# 15_HEATER.net
KiCad netlist of a schematic drawn in Altium Designer
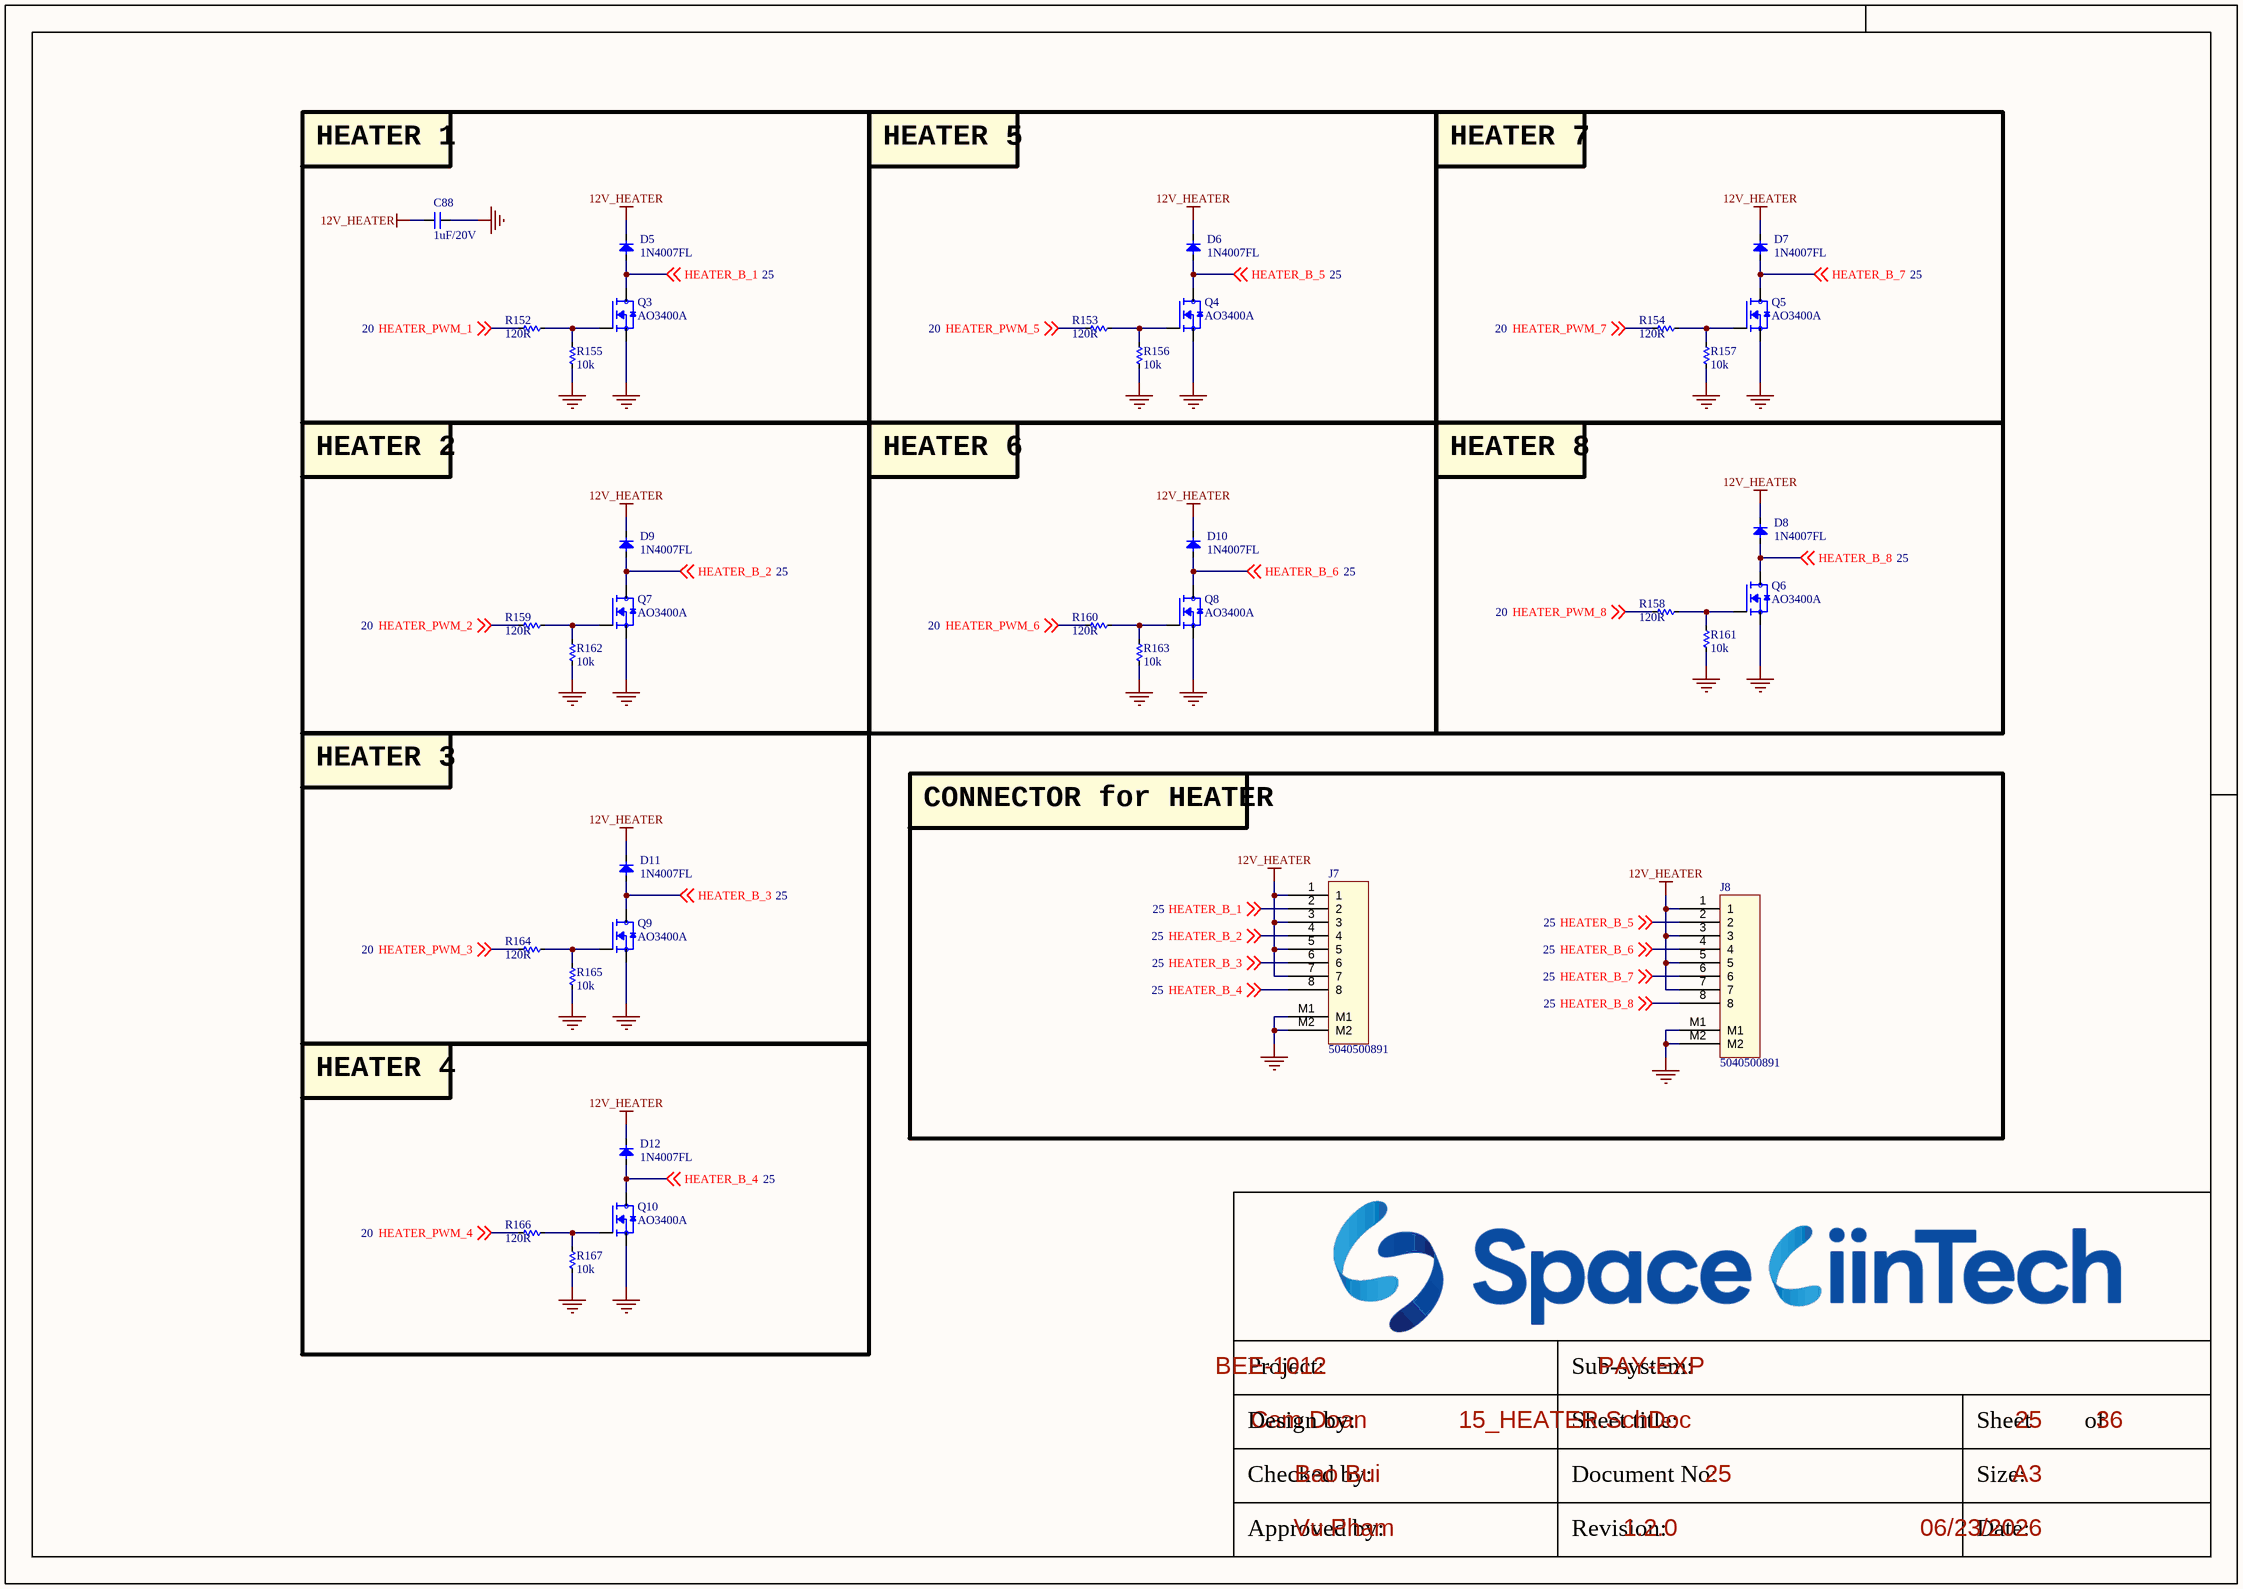
[diagram p0: 15_HEATER.SchDoc]

(export (version "E")
  (design (tool "Eeschema 10.0.6"))
  (components
    (comp (ref "C88")
      (value "1uF/20V")
      (footprint "CAP_C_1005X60")
      (description "CAP")
      (libsource (lib "LABLIB") (part "_CAP_C_2"))
    )
    (comp (ref "D5")
      (value "1N4007FL")
      (footprint "SOD3717X145N")
      (description "Default Diode")
      (fields (field (name "PUBLISHER") "Altium Limited"))
      (libsource (lib "LABLIB") (part "Diode SMD"))
    )
    (comp (ref "D6")
      (value "1N4007FL")
      (footprint "SOD3717X145N")
      (description "Default Diode")
      (fields (field (name "PUBLISHER") "Altium Limited"))
      (libsource (lib "LABLIB") (part "Diode SMD"))
    )
    (comp (ref "D7")
      (value "1N4007FL")
      (footprint "SOD3717X145N")
      (description "Default Diode")
      (fields (field (name "PUBLISHER") "Altium Limited"))
      (libsource (lib "LABLIB") (part "Diode SMD"))
    )
    (comp (ref "D8")
      (value "1N4007FL")
      (footprint "SOD3717X145N")
      (description "Default Diode")
      (fields (field (name "PUBLISHER") "Altium Limited"))
      (libsource (lib "LABLIB") (part "Diode SMD"))
    )
    (comp (ref "D9")
      (value "1N4007FL")
      (footprint "SOD3717X145N")
      (description "Default Diode")
      (fields (field (name "PUBLISHER") "Altium Limited"))
      (libsource (lib "LABLIB") (part "Diode SMD"))
    )
    (comp (ref "D10")
      (value "1N4007FL")
      (footprint "SOD3717X145N")
      (description "Default Diode")
      (fields (field (name "PUBLISHER") "Altium Limited"))
      (libsource (lib "LABLIB") (part "Diode SMD"))
    )
    (comp (ref "D11")
      (value "1N4007FL")
      (footprint "SOD3717X145N")
      (description "Default Diode")
      (fields (field (name "PUBLISHER") "Altium Limited"))
      (libsource (lib "LABLIB") (part "Diode SMD"))
    )
    (comp (ref "D12")
      (value "1N4007FL")
      (footprint "SOD3717X145N")
      (description "Default Diode")
      (fields (field (name "PUBLISHER") "Altium Limited"))
      (libsource (lib "LABLIB") (part "Diode SMD"))
    )
    (comp (ref "J7")
      (value "5040500891")
      (footprint "MOLEX_5040500891")
      (libsource (lib "LABLIB") (part "Header 8x1_2M"))
    )
    (comp (ref "J8")
      (value "5040500891")
      (footprint "MOLEX_5040500891")
      (libsource (lib "LABLIB") (part "Header 8x1_2M"))
    )
    (comp (ref "Q3")
      (value "AO3400A")
      (footprint "SOT95P240X120-3N")
      (description "N-Channel 30 V 5.7A (Ta) 1.4W (Ta) Surface Mount SOT-23-3")
      (fields (field (name "MF") "Alpha & Omega Semiconductor"))
      (libsource (lib "LABLIB") (part "MOSFET_N"))
    )
    (comp (ref "Q4")
      (value "AO3400A")
      (footprint "SOT95P240X120-3N")
      (description "N-Channel 30 V 5.7A (Ta) 1.4W (Ta) Surface Mount SOT-23-3")
      (fields (field (name "MF") "Alpha & Omega Semiconductor"))
      (libsource (lib "LABLIB") (part "MOSFET_N"))
    )
    (comp (ref "Q5")
      (value "AO3400A")
      (footprint "SOT95P240X120-3N")
      (description "N-Channel 30 V 5.7A (Ta) 1.4W (Ta) Surface Mount SOT-23-3")
      (fields (field (name "MF") "Alpha & Omega Semiconductor"))
      (libsource (lib "LABLIB") (part "MOSFET_N"))
    )
    (comp (ref "Q6")
      (value "AO3400A")
      (footprint "SOT95P240X120-3N")
      (description "N-Channel 30 V 5.7A (Ta) 1.4W (Ta) Surface Mount SOT-23-3")
      (fields (field (name "MF") "Alpha & Omega Semiconductor"))
      (libsource (lib "LABLIB") (part "MOSFET_N"))
    )
    (comp (ref "Q7")
      (value "AO3400A")
      (footprint "SOT95P240X120-3N")
      (description "N-Channel 30 V 5.7A (Ta) 1.4W (Ta) Surface Mount SOT-23-3")
      (fields (field (name "MF") "Alpha & Omega Semiconductor"))
      (libsource (lib "LABLIB") (part "MOSFET_N"))
    )
    (comp (ref "Q8")
      (value "AO3400A")
      (footprint "SOT95P240X120-3N")
      (description "N-Channel 30 V 5.7A (Ta) 1.4W (Ta) Surface Mount SOT-23-3")
      (fields (field (name "MF") "Alpha & Omega Semiconductor"))
      (libsource (lib "LABLIB") (part "MOSFET_N"))
    )
    (comp (ref "Q9")
      (value "AO3400A")
      (footprint "SOT95P240X120-3N")
      (description "N-Channel 30 V 5.7A (Ta) 1.4W (Ta) Surface Mount SOT-23-3")
      (fields (field (name "MF") "Alpha & Omega Semiconductor"))
      (libsource (lib "LABLIB") (part "MOSFET_N"))
    )
    (comp (ref "Q10")
      (value "AO3400A")
      (footprint "SOT95P240X120-3N")
      (description "N-Channel 30 V 5.7A (Ta) 1.4W (Ta) Surface Mount SOT-23-3")
      (fields (field (name "MF") "Alpha & Omega Semiconductor"))
      (libsource (lib "LABLIB") (part "MOSFET_N"))
    )
    (comp (ref "R152")
      (value "120R")
      (footprint "RES_C_1005X40")
      (description "RES")
      (libsource (lib "LABLIB") (part "_RES_B_2"))
    )
    (comp (ref "R153")
      (value "120R")
      (footprint "RES_C_1005X40")
      (description "RES")
      (libsource (lib "LABLIB") (part "_RES_B_2"))
    )
    (comp (ref "R154")
      (value "120R")
      (footprint "RES_C_1005X40")
      (description "RES")
      (libsource (lib "LABLIB") (part "_RES_B_2"))
    )
    (comp (ref "R155")
      (value "10k")
      (footprint "RES_C_1005X40")
      (description "RES")
      (libsource (lib "LABLIB") (part "_RES_B_2"))
    )
    (comp (ref "R156")
      (value "10k")
      (footprint "RES_C_1005X40")
      (description "RES")
      (libsource (lib "LABLIB") (part "_RES_B_2"))
    )
    (comp (ref "R157")
      (value "10k")
      (footprint "RES_C_1005X40")
      (description "RES")
      (libsource (lib "LABLIB") (part "_RES_B_2"))
    )
    (comp (ref "R158")
      (value "120R")
      (footprint "RES_C_1005X40")
      (description "RES")
      (libsource (lib "LABLIB") (part "_RES_B_2"))
    )
    (comp (ref "R159")
      (value "120R")
      (footprint "RES_C_1005X40")
      (description "RES")
      (libsource (lib "LABLIB") (part "_RES_B_2"))
    )
    (comp (ref "R160")
      (value "120R")
      (footprint "RES_C_1005X40")
      (description "RES")
      (libsource (lib "LABLIB") (part "_RES_B_2"))
    )
    (comp (ref "R161")
      (value "10k")
      (footprint "RES_C_1005X40")
      (description "RES")
      (libsource (lib "LABLIB") (part "_RES_B_2"))
    )
    (comp (ref "R162")
      (value "10k")
      (footprint "RES_C_1005X40")
      (description "RES")
      (libsource (lib "LABLIB") (part "_RES_B_2"))
    )
    (comp (ref "R163")
      (value "10k")
      (footprint "RES_C_1005X40")
      (description "RES")
      (libsource (lib "LABLIB") (part "_RES_B_2"))
    )
    (comp (ref "R164")
      (value "120R")
      (footprint "RES_C_1005X40")
      (description "RES")
      (libsource (lib "LABLIB") (part "_RES_B_2"))
    )
    (comp (ref "R165")
      (value "10k")
      (footprint "RES_C_1005X40")
      (description "RES")
      (libsource (lib "LABLIB") (part "_RES_B_2"))
    )
    (comp (ref "R166")
      (value "120R")
      (footprint "RES_C_1005X40")
      (description "RES")
      (libsource (lib "LABLIB") (part "_RES_B_2"))
    )
    (comp (ref "R167")
      (value "10k")
      (footprint "RES_C_1005X40")
      (description "RES")
      (libsource (lib "LABLIB") (part "_RES_B_2"))
    )
  )
  (nets
    (net (code "1") (name "12V_HEATER") (class "Default")
      (node (ref "C88") (pin "2") (pinfunction "2_2") (pintype "passive"))
      (node (ref "D10") (pin "1") (pinfunction "K_1") (pintype "passive"))
      (node (ref "D11") (pin "1") (pinfunction "K_1") (pintype "passive"))
      (node (ref "D12") (pin "1") (pinfunction "K_1") (pintype "passive"))
      (node (ref "D5") (pin "1") (pinfunction "K_1") (pintype "passive"))
      (node (ref "D6") (pin "1") (pinfunction "K_1") (pintype "passive"))
      (node (ref "D7") (pin "1") (pinfunction "K_1") (pintype "passive"))
      (node (ref "D8") (pin "1") (pinfunction "K_1") (pintype "passive"))
      (node (ref "D9") (pin "1") (pinfunction "K_1") (pintype "passive"))
      (node (ref "J7") (pin "1") (pinfunction "1_1") (pintype "passive"))
      (node (ref "J7") (pin "3") (pinfunction "3_3") (pintype "passive"))
      (node (ref "J7") (pin "5") (pinfunction "5_5") (pintype "passive"))
      (node (ref "J7") (pin "7") (pinfunction "7_7") (pintype "passive"))
      (node (ref "J8") (pin "1") (pinfunction "1_1") (pintype "passive"))
      (node (ref "J8") (pin "3") (pinfunction "3_3") (pintype "passive"))
      (node (ref "J8") (pin "5") (pinfunction "5_5") (pintype "passive"))
      (node (ref "J8") (pin "7") (pinfunction "7_7") (pintype "passive"))
    )
    (net (code "2") (name "GND") (class "Default")
      (node (ref "C88") (pin "1") (pinfunction "1_1") (pintype "passive"))
      (node (ref "J7") (pin "M1") (pinfunction "M1_M1") (pintype "passive"))
      (node (ref "J7") (pin "M2") (pinfunction "M2_M2") (pintype "passive"))
      (node (ref "J8") (pin "M1") (pinfunction "M1_M1") (pintype "passive"))
      (node (ref "J8") (pin "M2") (pinfunction "M2_M2") (pintype "passive"))
      (node (ref "Q10") (pin "2") (pinfunction "S_2") (pintype "passive"))
      (node (ref "Q3") (pin "2") (pinfunction "S_2") (pintype "passive"))
      (node (ref "Q4") (pin "2") (pinfunction "S_2") (pintype "passive"))
      (node (ref "Q5") (pin "2") (pinfunction "S_2") (pintype "passive"))
      (node (ref "Q6") (pin "2") (pinfunction "S_2") (pintype "passive"))
      (node (ref "Q7") (pin "2") (pinfunction "S_2") (pintype "passive"))
      (node (ref "Q8") (pin "2") (pinfunction "S_2") (pintype "passive"))
      (node (ref "Q9") (pin "2") (pinfunction "S_2") (pintype "passive"))
      (node (ref "R155") (pin "1") (pinfunction "1_1") (pintype "passive"))
      (node (ref "R156") (pin "1") (pinfunction "1_1") (pintype "passive"))
      (node (ref "R157") (pin "1") (pinfunction "1_1") (pintype "passive"))
      (node (ref "R161") (pin "1") (pinfunction "1_1") (pintype "passive"))
      (node (ref "R162") (pin "1") (pinfunction "1_1") (pintype "passive"))
      (node (ref "R163") (pin "1") (pinfunction "1_1") (pintype "passive"))
      (node (ref "R165") (pin "1") (pinfunction "1_1") (pintype "passive"))
      (node (ref "R167") (pin "1") (pinfunction "1_1") (pintype "passive"))
    )
    (net (code "3") (name "HEATER_B_1") (class "Default")
      (node (ref "D5") (pin "2") (pinfunction "A_2") (pintype "passive"))
      (node (ref "J7") (pin "2") (pinfunction "2_2") (pintype "passive"))
      (node (ref "Q3") (pin "3") (pinfunction "D_3") (pintype "passive"))
    )
    (net (code "4") (name "HEATER_B_2") (class "Default")
      (node (ref "D9") (pin "2") (pinfunction "A_2") (pintype "passive"))
      (node (ref "J7") (pin "4") (pinfunction "4_4") (pintype "passive"))
      (node (ref "Q7") (pin "3") (pinfunction "D_3") (pintype "passive"))
    )
    (net (code "5") (name "HEATER_B_3") (class "Default")
      (node (ref "D11") (pin "2") (pinfunction "A_2") (pintype "passive"))
      (node (ref "J7") (pin "6") (pinfunction "6_6") (pintype "passive"))
      (node (ref "Q9") (pin "3") (pinfunction "D_3") (pintype "passive"))
    )
    (net (code "6") (name "HEATER_B_4") (class "Default")
      (node (ref "D12") (pin "2") (pinfunction "A_2") (pintype "passive"))
      (node (ref "J7") (pin "8") (pinfunction "8_8") (pintype "passive"))
      (node (ref "Q10") (pin "3") (pinfunction "D_3") (pintype "passive"))
    )
    (net (code "7") (name "HEATER_B_5") (class "Default")
      (node (ref "D6") (pin "2") (pinfunction "A_2") (pintype "passive"))
      (node (ref "J8") (pin "2") (pinfunction "2_2") (pintype "passive"))
      (node (ref "Q4") (pin "3") (pinfunction "D_3") (pintype "passive"))
    )
    (net (code "8") (name "HEATER_B_6") (class "Default")
      (node (ref "D10") (pin "2") (pinfunction "A_2") (pintype "passive"))
      (node (ref "J8") (pin "4") (pinfunction "4_4") (pintype "passive"))
      (node (ref "Q8") (pin "3") (pinfunction "D_3") (pintype "passive"))
    )
    (net (code "9") (name "HEATER_B_7") (class "Default")
      (node (ref "D7") (pin "2") (pinfunction "A_2") (pintype "passive"))
      (node (ref "J8") (pin "6") (pinfunction "6_6") (pintype "passive"))
      (node (ref "Q5") (pin "3") (pinfunction "D_3") (pintype "passive"))
    )
    (net (code "10") (name "HEATER_B_8") (class "Default")
      (node (ref "D8") (pin "2") (pinfunction "A_2") (pintype "passive"))
      (node (ref "J8") (pin "8") (pinfunction "8_8") (pintype "passive"))
      (node (ref "Q6") (pin "3") (pinfunction "D_3") (pintype "passive"))
    )
    (net (code "11") (name "HEATER_PWM_1") (class "Default")
      (node (ref "R152") (pin "1") (pinfunction "1_1") (pintype "passive"))
    )
    (net (code "12") (name "HEATER_PWM_2") (class "Default")
      (node (ref "R159") (pin "1") (pinfunction "1_1") (pintype "passive"))
    )
    (net (code "13") (name "HEATER_PWM_3") (class "Default")
      (node (ref "R164") (pin "1") (pinfunction "1_1") (pintype "passive"))
    )
    (net (code "14") (name "HEATER_PWM_4") (class "Default")
      (node (ref "R166") (pin "1") (pinfunction "1_1") (pintype "passive"))
    )
    (net (code "15") (name "HEATER_PWM_5") (class "Default")
      (node (ref "R153") (pin "1") (pinfunction "1_1") (pintype "passive"))
    )
    (net (code "16") (name "HEATER_PWM_6") (class "Default")
      (node (ref "R160") (pin "1") (pinfunction "1_1") (pintype "passive"))
    )
    (net (code "17") (name "HEATER_PWM_7") (class "Default")
      (node (ref "R154") (pin "1") (pinfunction "1_1") (pintype "passive"))
    )
    (net (code "18") (name "HEATER_PWM_8") (class "Default")
      (node (ref "R158") (pin "1") (pinfunction "1_1") (pintype "passive"))
    )
    (net (code "19") (name "Net-(Q3-G)") (class "Default")
      (node (ref "Q3") (pin "1") (pinfunction "G_1") (pintype "passive"))
      (node (ref "R152") (pin "2") (pinfunction "2_2") (pintype "passive"))
      (node (ref "R155") (pin "2") (pinfunction "2_2") (pintype "passive"))
    )
    (net (code "20") (name "Net-(Q4-G)") (class "Default")
      (node (ref "Q4") (pin "1") (pinfunction "G_1") (pintype "passive"))
      (node (ref "R153") (pin "2") (pinfunction "2_2") (pintype "passive"))
      (node (ref "R156") (pin "2") (pinfunction "2_2") (pintype "passive"))
    )
    (net (code "21") (name "Net-(Q5-G)") (class "Default")
      (node (ref "Q5") (pin "1") (pinfunction "G_1") (pintype "passive"))
      (node (ref "R154") (pin "2") (pinfunction "2_2") (pintype "passive"))
      (node (ref "R157") (pin "2") (pinfunction "2_2") (pintype "passive"))
    )
    (net (code "22") (name "Net-(Q6-G)") (class "Default")
      (node (ref "Q6") (pin "1") (pinfunction "G_1") (pintype "passive"))
      (node (ref "R158") (pin "2") (pinfunction "2_2") (pintype "passive"))
      (node (ref "R161") (pin "2") (pinfunction "2_2") (pintype "passive"))
    )
    (net (code "23") (name "Net-(Q7-G)") (class "Default")
      (node (ref "Q7") (pin "1") (pinfunction "G_1") (pintype "passive"))
      (node (ref "R159") (pin "2") (pinfunction "2_2") (pintype "passive"))
      (node (ref "R162") (pin "2") (pinfunction "2_2") (pintype "passive"))
    )
    (net (code "24") (name "Net-(Q8-G)") (class "Default")
      (node (ref "Q8") (pin "1") (pinfunction "G_1") (pintype "passive"))
      (node (ref "R160") (pin "2") (pinfunction "2_2") (pintype "passive"))
      (node (ref "R163") (pin "2") (pinfunction "2_2") (pintype "passive"))
    )
    (net (code "25") (name "Net-(Q9-G)") (class "Default")
      (node (ref "Q9") (pin "1") (pinfunction "G_1") (pintype "passive"))
      (node (ref "R164") (pin "2") (pinfunction "2_2") (pintype "passive"))
      (node (ref "R165") (pin "2") (pinfunction "2_2") (pintype "passive"))
    )
    (net (code "26") (name "Net-(Q10-G)") (class "Default")
      (node (ref "Q10") (pin "1") (pinfunction "G_1") (pintype "passive"))
      (node (ref "R166") (pin "2") (pinfunction "2_2") (pintype "passive"))
      (node (ref "R167") (pin "2") (pinfunction "2_2") (pintype "passive"))
    )
  )
)
